# UART_Bus.net
KiCad netlist of a schematic drawn in Altium Designer
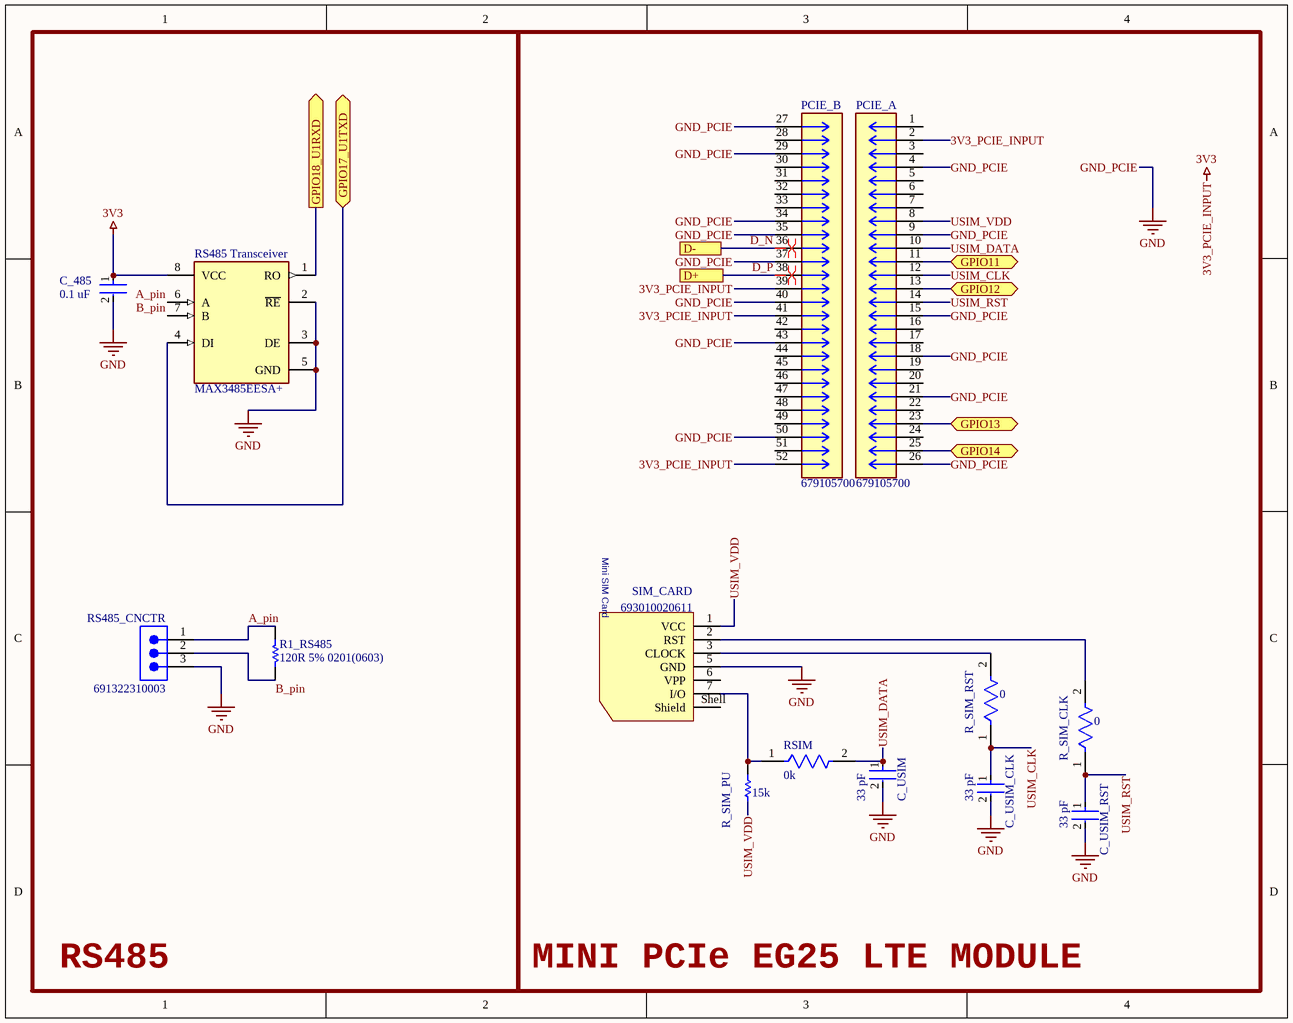
[diagram p0: UART Bus.SchDoc]

(export (version "E")
  (design (tool "Eeschema 10.0.6"))
  (components
    (comp (ref "C_485")
      (value "0.1 uF")
      (footprint "FP-GRM155-0_05-MFG")
      (description "Chip Multilayer Ceramic Capacitors for General Purpose, 0402, 0.10uF, X7R, 15%, 20%, 50V")
      (libsource (lib "Altium Content Vault") (part "02cd4be3c70576c341d710602a673aa"))
    )
    (comp (ref "C_USIM")
      (value "33 pF")
      (footprint "FP-GCM155-0_05-IPC_A")
      (description "Ceramic Capacitor for Automotive 33pF ±5% 50VDC C0G 0402 Paper T/R")
      (fields (field (name "TOLERANCE") "5%"))
      (libsource (lib "Altium Content Vault") (part "02cd4be3c70576c341d710602a673aa"))
    )
    (comp (ref "C_USIM_CLK")
      (value "33 pF")
      (footprint "FP-GCM155-0_05-IPC_A")
      (description "Ceramic Capacitor for Automotive 33pF ±5% 50VDC C0G 0402 Paper T/R")
      (fields (field (name "TOLERANCE") "5%"))
      (libsource (lib "Altium Content Vault") (part "02cd4be3c70576c341d710602a673aa"))
    )
    (comp (ref "C_USIM_RST")
      (value "33 pF")
      (footprint "FP-GCM155-0_05-IPC_A")
      (description "Ceramic Capacitor for Automotive 33pF ±5% 50VDC C0G 0402 Paper T/R")
      (fields (field (name "TOLERANCE") "5%"))
      (libsource (lib "Altium Content Vault") (part "02cd4be3c70576c341d710602a673aa"))
    )
    (comp (ref "PCIE_")
      (value "679105700")
      (footprint "CONN_679105700_MOL")
      (libsource (lib "Faiz Agunda") (part "679105700"))
    )
    (comp (ref "R1_RS485")
      (value "120R 5% 0201(0603)")
      (footprint "RESC0201(0603)_M")
      (description "120R 0.05W 5% 0201 (0603 Metric)  SMD")
      (fields (field (name "POWER") "0.05 W") (field (name "TOLERANCE") "5 %"))
      (libsource (lib "Altium Content Vault") (part "RES"))
    )
    (comp (ref "RS485 Transceiver")
      (value "MAX3485EESA+")
      (footprint "FP-S8-5-MFG")
      (description "IC TXRX RS485/422 10MBPS 8SOIC")
      (fields
        (field (name "OCTOPART") "https://octopart.com/max3485eesa%2B-maxim+integrated-39731903")
        (field (name "MANUFACTURER") "Maxim Integrated")
      )
      (libsource (lib "Altium Content Vault") (part "be0caabdb159a9a12bcb36ec340889e"))
    )
    (comp (ref "RS485_CNCTR")
      (value "691322310003")
      (footprint "691322310003")
      (description "322; 3.81mm Pitch Straight Pluggable Term Block; PCB Header; Through Hole; 3 Way")
      (fields (field (name "VOLTAGE") "300V"))
      (libsource (lib "Altium Content Vault") (part "TBL - 1R - 03P - Male"))
    )
    (comp (ref "RSIM")
      (value "0k")
      (footprint "FP-CRG0402-IPC_C")
      (description "RES SMD 0 OHM JUMPER 1/16W 0402")
      (fields (field (name "TOLERANCE") "0%"))
      (libsource (lib "Altium Content Vault") (part "1029c3af85768c4190bb7ad29bc67b5"))
    )
    (comp (ref "R_SIM_CLK")
      (value "0")
      (footprint "FP-CRG0402-IPC_C")
      (description "RES SMD 0 OHM JUMPER 1/16W 0402")
      (fields (field (name "TOLERANCE") "0%"))
      (libsource (lib "Altium Content Vault") (part "1029c3af85768c4190bb7ad29bc67b5"))
    )
    (comp (ref "R_SIM_PU")
      (value "15k")
      (footprint "RESC3116X65X40NL10T20")
      (fields (field (name "MANUFACTURER") "Yageo") (field (name "PART NUMBER") "RC1206FR-1015KL"))
      (libsource (lib "Altium Content Vault") (part "RES"))
    )
    (comp (ref "R_SIM_RST")
      (value "0")
      (footprint "FP-CRG0402-IPC_C")
      (description "RES SMD 0 OHM JUMPER 1/16W 0402")
      (fields (field (name "TOLERANCE") "0%"))
      (libsource (lib "Altium Content Vault") (part "1029c3af85768c4190bb7ad29bc67b5"))
    )
    (comp (ref "SIM_CARD")
      (value "693010020611")
      (footprint "693010020611")
      (description "WR-CRD Mini SIM Card Connector Header Shielded")
      (libsource (lib "Altium Content Vault") (part "Mini SIM Card Socket_693010020611"))
    )
  )
  (nets
    (net (code "1") (name "/A_pin") (class "Default")
      (node (ref "R1_RS485") (pin "1") (pinfunction "1_1") (pintype "passive"))
      (node (ref "RS485 Transceiver") (pin "6") (pinfunction "A_6") (pintype "input"))
      (node (ref "RS485_CNCTR") (pin "1") (pinfunction "1_1") (pintype "passive"))
    )
    (net (code "2") (name "/B_pin") (class "Default")
      (node (ref "R1_RS485") (pin "2") (pinfunction "2_2") (pintype "passive"))
      (node (ref "RS485 Transceiver") (pin "7") (pinfunction "B_7") (pintype "input"))
      (node (ref "RS485_CNCTR") (pin "2") (pinfunction "2_2") (pintype "passive"))
    )
    (net (code "3") (name "/D_N") (class "Default")
      (node (ref "PCIE_") (pin "36") (pinfunction "36_36") (pintype "passive"))
    )
    (net (code "4") (name "/D_P") (class "Default")
      (node (ref "PCIE_") (pin "38") (pinfunction "38_38") (pintype "passive"))
    )
    (net (code "5") (name "/GPIO11") (class "Default")
      (node (ref "PCIE_") (pin "11") (pinfunction "11_11") (pintype "passive"))
    )
    (net (code "6") (name "/GPIO12") (class "Default")
      (node (ref "PCIE_") (pin "13") (pinfunction "13_13") (pintype "passive"))
    )
    (net (code "7") (name "/GPIO13") (class "Default")
      (node (ref "PCIE_") (pin "23") (pinfunction "23_23") (pintype "passive"))
    )
    (net (code "8") (name "/GPIO14") (class "Default")
      (node (ref "PCIE_") (pin "25") (pinfunction "25_25") (pintype "passive"))
    )
    (net (code "9") (name "/GPIO17_U1TXD") (class "Default")
      (node (ref "RS485 Transceiver") (pin "4") (pinfunction "DI_4") (pintype "input"))
    )
    (net (code "10") (name "/GPIO18_U1RXD") (class "Default")
      (node (ref "RS485 Transceiver") (pin "1") (pinfunction "RO_1") (pintype "output"))
    )
    (net (code "11") (name "/USIM_CLK") (class "Default")
      (node (ref "C_USIM_CLK") (pin "1") (pinfunction "1_1") (pintype "passive"))
      (node (ref "PCIE_") (pin "12") (pinfunction "12_12") (pintype "passive"))
      (node (ref "R_SIM_RST") (pin "1") (pinfunction "1_1") (pintype "passive"))
    )
    (net (code "12") (name "/USIM_DATA") (class "Default")
      (node (ref "C_USIM") (pin "1") (pinfunction "1_1") (pintype "passive"))
      (node (ref "PCIE_") (pin "10") (pinfunction "10_10") (pintype "passive"))
      (node (ref "RSIM") (pin "2") (pinfunction "2_2") (pintype "passive"))
    )
    (net (code "13") (name "/USIM_RST") (class "Default")
      (node (ref "C_USIM_RST") (pin "1") (pinfunction "1_1") (pintype "passive"))
      (node (ref "PCIE_") (pin "14") (pinfunction "14_14") (pintype "passive"))
      (node (ref "R_SIM_CLK") (pin "1") (pinfunction "1_1") (pintype "passive"))
    )
    (net (code "14") (name "/USIM_VDD") (class "Default")
      (node (ref "PCIE_") (pin "8") (pinfunction "8_8") (pintype "passive"))
      (node (ref "R_SIM_PU") (pin "2") (pinfunction "2_2") (pintype "passive"))
      (node (ref "SIM_CARD") (pin "1") (pinfunction "VCC_1") (pintype "passive"))
    )
    (net (code "15") (name "3V3") (class "Default")
      (node (ref "C_485") (pin "1") (pinfunction "1_1") (pintype "passive"))
      (node (ref "PCIE_") (pin "2") (pinfunction "2_2") (pintype "passive"))
      (node (ref "PCIE_") (pin "39") (pinfunction "39_39") (pintype "passive"))
      (node (ref "PCIE_") (pin "41") (pinfunction "41_41") (pintype "passive"))
      (node (ref "PCIE_") (pin "52") (pinfunction "52_52") (pintype "passive"))
      (node (ref "RS485 Transceiver") (pin "8") (pinfunction "VCC_8") (pintype "power_in"))
    )
    (net (code "16") (name "GND") (class "Default")
      (node (ref "C_485") (pin "2") (pinfunction "2_2") (pintype "passive"))
      (node (ref "C_USIM") (pin "2") (pinfunction "2_2") (pintype "passive"))
      (node (ref "C_USIM_CLK") (pin "2") (pinfunction "2_2") (pintype "passive"))
      (node (ref "C_USIM_RST") (pin "2") (pinfunction "2_2") (pintype "passive"))
      (node (ref "PCIE_") (pin "15") (pinfunction "15_15") (pintype "passive"))
      (node (ref "PCIE_") (pin "18") (pinfunction "18_18") (pintype "passive"))
      (node (ref "PCIE_") (pin "21") (pinfunction "21_21") (pintype "passive"))
      (node (ref "PCIE_") (pin "26") (pinfunction "26_26") (pintype "passive"))
      (node (ref "PCIE_") (pin "27") (pinfunction "27_27") (pintype "passive"))
      (node (ref "PCIE_") (pin "29") (pinfunction "29_29") (pintype "passive"))
      (node (ref "PCIE_") (pin "34") (pinfunction "34_34") (pintype "passive"))
      (node (ref "PCIE_") (pin "35") (pinfunction "35_35") (pintype "passive"))
      (node (ref "PCIE_") (pin "37") (pinfunction "37_37") (pintype "passive"))
      (node (ref "PCIE_") (pin "4") (pinfunction "4_4") (pintype "passive"))
      (node (ref "PCIE_") (pin "40") (pinfunction "40_40") (pintype "passive"))
      (node (ref "PCIE_") (pin "43") (pinfunction "43_43") (pintype "passive"))
      (node (ref "PCIE_") (pin "50") (pinfunction "50_50") (pintype "passive"))
      (node (ref "PCIE_") (pin "9") (pinfunction "9_9") (pintype "passive"))
      (node (ref "RS485 Transceiver") (pin "2") (pinfunction "~{RE}_2") (pintype "passive"))
      (node (ref "RS485 Transceiver") (pin "3") (pinfunction "DE_3") (pintype "passive"))
      (node (ref "RS485 Transceiver") (pin "5") (pinfunction "GND_5") (pintype "power_in"))
      (node (ref "RS485_CNCTR") (pin "3") (pinfunction "3_3") (pintype "passive"))
      (node (ref "SIM_CARD") (pin "5") (pinfunction "GND_5") (pintype "passive"))
    )
    (net (code "17") (name "Net-(SIM_CARD-CLOCK)") (class "Default")
      (node (ref "R_SIM_RST") (pin "2") (pinfunction "2_2") (pintype "passive"))
      (node (ref "SIM_CARD") (pin "3") (pinfunction "CLOCK_3") (pintype "passive"))
    )
    (net (code "18") (name "Net-(SIM_CARD-I{slash}O)") (class "Default")
      (node (ref "RSIM") (pin "1") (pinfunction "1_1") (pintype "passive"))
      (node (ref "R_SIM_PU") (pin "1") (pinfunction "1_1") (pintype "passive"))
      (node (ref "SIM_CARD") (pin "7") (pinfunction "I/O_7") (pintype "passive"))
    )
    (net (code "19") (name "Net-(SIM_CARD-RST)") (class "Default")
      (node (ref "R_SIM_CLK") (pin "2") (pinfunction "2_2") (pintype "passive"))
      (node (ref "SIM_CARD") (pin "2") (pinfunction "RST_2") (pintype "passive"))
    )
    (net (code "20") (name "unconnected-(PCIE_-Pad1)") (class "Default")
      (node (ref "PCIE_") (pin "1") (pinfunction "1_1") (pintype "passive"))
    )
    (net (code "21") (name "unconnected-(PCIE_-Pad3)") (class "Default")
      (node (ref "PCIE_") (pin "3") (pinfunction "3_3") (pintype "passive"))
    )
    (net (code "22") (name "unconnected-(PCIE_-Pad5)") (class "Default")
      (node (ref "PCIE_") (pin "5") (pinfunction "5_5") (pintype "passive"))
    )
    (net (code "23") (name "unconnected-(PCIE_-Pad6)") (class "Default")
      (node (ref "PCIE_") (pin "6") (pinfunction "6_6") (pintype "passive"))
    )
    (net (code "24") (name "unconnected-(PCIE_-Pad7)") (class "Default")
      (node (ref "PCIE_") (pin "7") (pinfunction "7_7") (pintype "passive"))
    )
    (net (code "25") (name "unconnected-(PCIE_-Pad16)") (class "Default")
      (node (ref "PCIE_") (pin "16") (pinfunction "16_16") (pintype "passive"))
    )
    (net (code "26") (name "unconnected-(PCIE_-Pad17)") (class "Default")
      (node (ref "PCIE_") (pin "17") (pinfunction "17_17") (pintype "passive"))
    )
    (net (code "27") (name "unconnected-(PCIE_-Pad19)") (class "Default")
      (node (ref "PCIE_") (pin "19") (pinfunction "19_19") (pintype "passive"))
    )
    (net (code "28") (name "unconnected-(PCIE_-Pad20)") (class "Default")
      (node (ref "PCIE_") (pin "20") (pinfunction "20_20") (pintype "passive"))
    )
    (net (code "29") (name "unconnected-(PCIE_-Pad22)") (class "Default")
      (node (ref "PCIE_") (pin "22") (pinfunction "22_22") (pintype "passive"))
    )
    (net (code "30") (name "unconnected-(PCIE_-Pad24)") (class "Default")
      (node (ref "PCIE_") (pin "24") (pinfunction "24_24") (pintype "passive"))
    )
    (net (code "31") (name "unconnected-(PCIE_-Pad28)") (class "Default")
      (node (ref "PCIE_") (pin "28") (pinfunction "28_28") (pintype "passive"))
    )
    (net (code "32") (name "unconnected-(PCIE_-Pad30)") (class "Default")
      (node (ref "PCIE_") (pin "30") (pinfunction "30_30") (pintype "passive"))
    )
    (net (code "33") (name "unconnected-(PCIE_-Pad31)") (class "Default")
      (node (ref "PCIE_") (pin "31") (pinfunction "31_31") (pintype "passive"))
    )
    (net (code "34") (name "unconnected-(PCIE_-Pad32)") (class "Default")
      (node (ref "PCIE_") (pin "32") (pinfunction "32_32") (pintype "passive"))
    )
    (net (code "35") (name "unconnected-(PCIE_-Pad33)") (class "Default")
      (node (ref "PCIE_") (pin "33") (pinfunction "33_33") (pintype "passive"))
    )
    (net (code "36") (name "unconnected-(PCIE_-Pad42)") (class "Default")
      (node (ref "PCIE_") (pin "42") (pinfunction "42_42") (pintype "passive"))
    )
    (net (code "37") (name "unconnected-(PCIE_-Pad44)") (class "Default")
      (node (ref "PCIE_") (pin "44") (pinfunction "44_44") (pintype "passive"))
    )
    (net (code "38") (name "unconnected-(PCIE_-Pad45)") (class "Default")
      (node (ref "PCIE_") (pin "45") (pinfunction "45_45") (pintype "passive"))
    )
    (net (code "39") (name "unconnected-(PCIE_-Pad46)") (class "Default")
      (node (ref "PCIE_") (pin "46") (pinfunction "46_46") (pintype "passive"))
    )
    (net (code "40") (name "unconnected-(PCIE_-Pad47)") (class "Default")
      (node (ref "PCIE_") (pin "47") (pinfunction "47_47") (pintype "passive"))
    )
    (net (code "41") (name "unconnected-(PCIE_-Pad48)") (class "Default")
      (node (ref "PCIE_") (pin "48") (pinfunction "48_48") (pintype "passive"))
    )
    (net (code "42") (name "unconnected-(PCIE_-Pad49)") (class "Default")
      (node (ref "PCIE_") (pin "49") (pinfunction "49_49") (pintype "passive"))
    )
    (net (code "43") (name "unconnected-(PCIE_-Pad51)") (class "Default")
      (node (ref "PCIE_") (pin "51") (pinfunction "51_51") (pintype "passive"))
    )
    (net (code "44") (name "unconnected-(SIM_CARD-Shield-PadShell)") (class "Default")
      (node (ref "SIM_CARD") (pin "Shell") (pinfunction "Shield_Shell") (pintype "passive"))
    )
    (net (code "45") (name "unconnected-(SIM_CARD-VPP-Pad6)") (class "Default")
      (node (ref "SIM_CARD") (pin "6") (pinfunction "VPP_6") (pintype "passive"))
    )
  )
)
